# Control_Board_v0_2.net
KiCad netlist of a schematic drawn in EAGLE
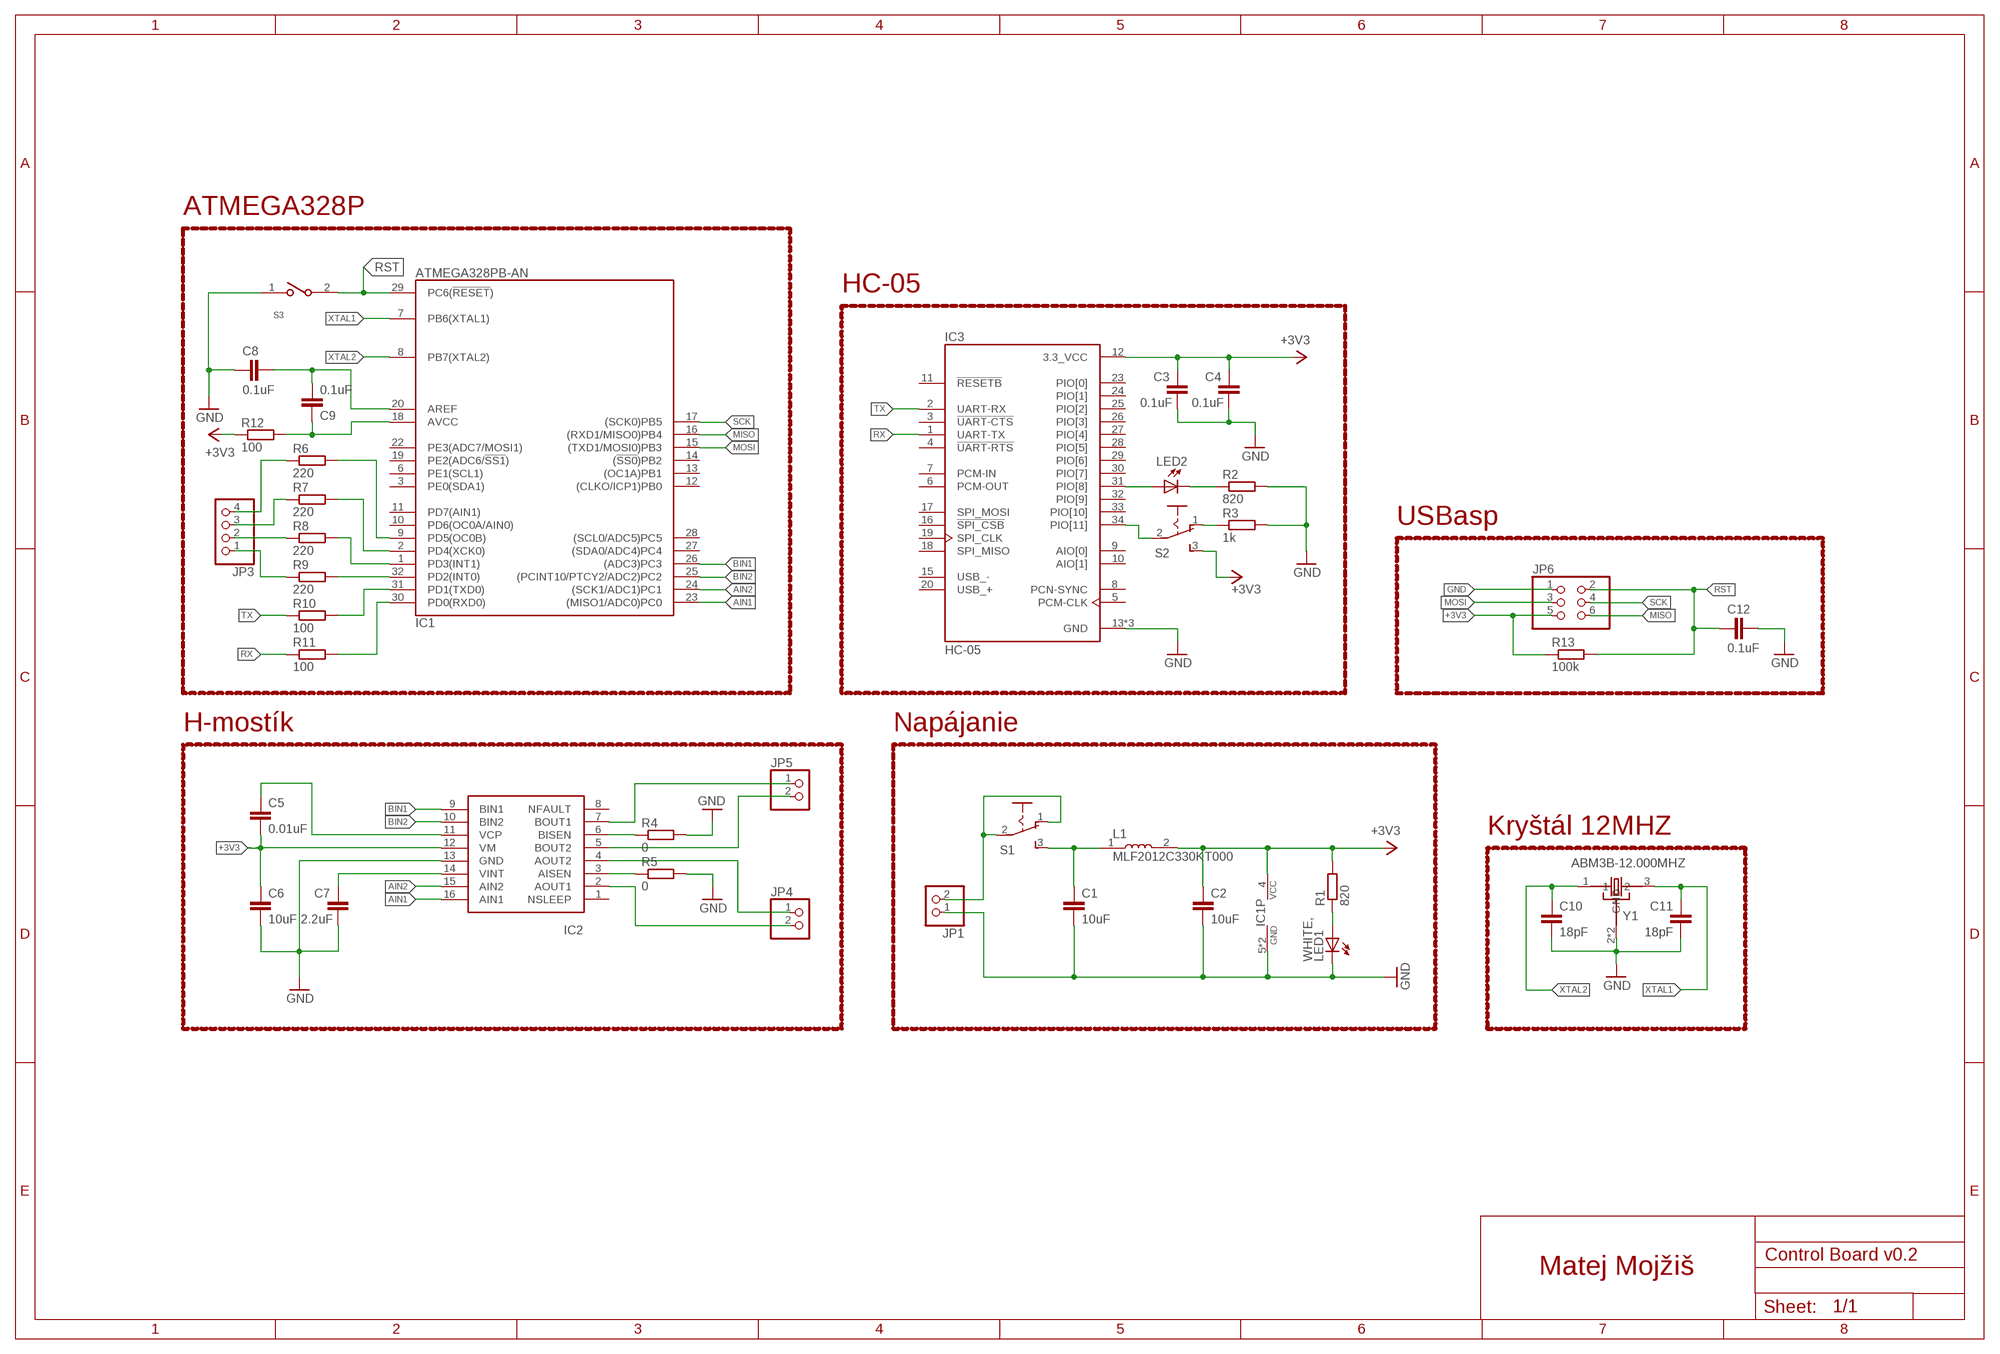
[diagram p0: schematic, sheet 1]

(export (version "E")
  (design (tool "Eeschema 10.0.6"))
  (components
    (comp (ref "C1")
      (value "10uF")
      (footprint "eagle-import:C0805")
      (libsource (lib "eagle-import") (part "C-EUC0805"))
    )
    (comp (ref "C2")
      (value "10uF")
      (footprint "eagle-import:C0805")
      (libsource (lib "eagle-import") (part "C-EUC0805"))
    )
    (comp (ref "C3")
      (value "0.1uF")
      (footprint "eagle-import:C0805")
      (libsource (lib "eagle-import") (part "C-EUC0805"))
    )
    (comp (ref "C4")
      (value "0.1uF")
      (footprint "eagle-import:C0805")
      (libsource (lib "eagle-import") (part "C-EUC0805"))
    )
    (comp (ref "C5")
      (value "0.01uF")
      (footprint "eagle-import:C0805")
      (libsource (lib "eagle-import") (part "C-EUC0805"))
    )
    (comp (ref "C6")
      (value "10uF")
      (footprint "eagle-import:C0805")
      (libsource (lib "eagle-import") (part "C-EUC0805"))
    )
    (comp (ref "C7")
      (value "2.2uF")
      (footprint "eagle-import:C0805")
      (libsource (lib "eagle-import") (part "C-EUC0805"))
    )
    (comp (ref "C8")
      (value "0.1uF")
      (footprint "eagle-import:C0805")
      (libsource (lib "eagle-import") (part "C-EUC0805"))
    )
    (comp (ref "C9")
      (value "0.1uF")
      (footprint "eagle-import:C0805")
      (libsource (lib "eagle-import") (part "C-EUC0805"))
    )
    (comp (ref "C10")
      (value "18pF")
      (footprint "eagle-import:C0805")
      (libsource (lib "eagle-import") (part "C-EUC0805"))
    )
    (comp (ref "C11")
      (value "18pF")
      (footprint "eagle-import:C0805")
      (libsource (lib "eagle-import") (part "C-EUC0805"))
    )
    (comp (ref "C12")
      (value "0.1uF")
      (footprint "eagle-import:C0805")
      (libsource (lib "eagle-import") (part "C-EUC0805"))
    )
    (comp (ref "IC1")
      (value "ATMEGA328PB-AN")
      (footprint "eagle-import:QFP32_7X7_0.80")
      (libsource (lib "eagle-import") (part "ATMEGA328PB-AN"))
    )
    (comp (ref "IC2")
      (value "DVR8833SUPERFICIAL")
      (footprint "eagle-import:PWP16")
      (libsource (lib "eagle-import") (part "DVR8833SUPERFICIAL"))
    )
    (comp (ref "IC3")
      (value "HC-05")
      (footprint "eagle-import:XCVR_HC-05")
      (fields (field (name "MF") "Bel Power solution"))
      (libsource (lib "eagle-import") (part "HC-05"))
    )
    (comp (ref "JP1")
      (value "PINHD-1X2/90")
      (footprint "eagle-import:1X02_90")
      (libsource (lib "eagle-import") (part "PINHD-1X2/90"))
    )
    (comp (ref "JP3")
      (value "PINHD-1X4")
      (footprint "eagle-import:1X04")
      (libsource (lib "eagle-import") (part "PINHD-1X4"))
    )
    (comp (ref "JP4")
      (value "PINHD-1X2/90")
      (footprint "eagle-import:1X02_90")
      (libsource (lib "eagle-import") (part "PINHD-1X2/90"))
    )
    (comp (ref "JP5")
      (value "PINHD-1X2/90")
      (footprint "eagle-import:1X02_90")
      (libsource (lib "eagle-import") (part "PINHD-1X2/90"))
    )
    (comp (ref "JP6")
      (value "PINHD-2X3")
      (footprint "eagle-import:2X03")
      (libsource (lib "eagle-import") (part "PINHD-2X3"))
    )
    (comp (ref "L1")
      (value "MLF2012C330KT000")
      (footprint "eagle-import:INDC2012X87N")
      (fields (field (name "MF") "TDK"))
      (libsource (lib "eagle-import") (part "MLF2012C330KT000"))
    )
    (comp (ref "LED1")
      (value "WHITE,")
      (footprint "eagle-import:CHIPLED_0805")
      (libsource (lib "eagle-import") (part "LEDCHIPLED_0805"))
    )
    (comp (ref "LED2")
      (value "RED")
      (footprint "eagle-import:CHIPLED_0805")
      (libsource (lib "eagle-import") (part "LEDCHIPLED_0805"))
    )
    (comp (ref "R1")
      (value "820")
      (footprint "eagle-import:R0805")
      (libsource (lib "eagle-import") (part "R-EU_R0805"))
    )
    (comp (ref "R2")
      (value "820")
      (footprint "eagle-import:R0805")
      (libsource (lib "eagle-import") (part "R-EU_R0805"))
    )
    (comp (ref "R3")
      (value "1k")
      (footprint "eagle-import:R0805")
      (libsource (lib "eagle-import") (part "R-EU_R0805"))
    )
    (comp (ref "R4")
      (value "0")
      (footprint "eagle-import:R0805")
      (libsource (lib "eagle-import") (part "R-EU_R0805"))
    )
    (comp (ref "R5")
      (value "0")
      (footprint "eagle-import:R0805")
      (libsource (lib "eagle-import") (part "R-EU_R0805"))
    )
    (comp (ref "R6")
      (value "220")
      (footprint "eagle-import:R0805")
      (libsource (lib "eagle-import") (part "R-EU_R0805"))
    )
    (comp (ref "R7")
      (value "220")
      (footprint "eagle-import:R0805")
      (libsource (lib "eagle-import") (part "R-EU_R0805"))
    )
    (comp (ref "R8")
      (value "220")
      (footprint "eagle-import:R0805")
      (libsource (lib "eagle-import") (part "R-EU_R0805"))
    )
    (comp (ref "R9")
      (value "220")
      (footprint "eagle-import:R0805")
      (libsource (lib "eagle-import") (part "R-EU_R0805"))
    )
    (comp (ref "R10")
      (value "100")
      (footprint "eagle-import:R0805")
      (libsource (lib "eagle-import") (part "R-EU_R0805"))
    )
    (comp (ref "R11")
      (value "100")
      (footprint "eagle-import:R0805")
      (libsource (lib "eagle-import") (part "R-EU_R0805"))
    )
    (comp (ref "R12")
      (value "100")
      (footprint "eagle-import:R0805")
      (libsource (lib "eagle-import") (part "R-EU_R0805"))
    )
    (comp (ref "R13")
      (value "100k")
      (footprint "eagle-import:R0805")
      (libsource (lib "eagle-import") (part "R-EU_R0805"))
    )
    (comp (ref "S1")
      (value "255SB")
      (footprint "eagle-import:255SB")
      (libsource (lib "eagle-import") (part "255SB"))
    )
    (comp (ref "S2")
      (value "255SB")
      (footprint "eagle-import:255SB")
      (libsource (lib "eagle-import") (part "255SB"))
    )
    (comp (ref "S3")
      (value "147873-2")
      (footprint "eagle-import:SW_147873-2")
      (fields (field (name "MF") "TE Connectivity"))
      (libsource (lib "eagle-import") (part "147873-2"))
    )
    (comp (ref "Y1")
      (value "ABM3B-12.000MHZ")
      (footprint "eagle-import:OSCSC500X320X110-4N")
      (fields (field (name "MF") "Abracon") (field (name "MP") "ABM3B-8.000MHZ-B2-T"))
      (libsource (lib "eagle-import") (part "ABM3B-8.000MHZ-B2-T"))
    )
  )
  (nets
    (net (code "1") (name "+3V3") (class "Default")
      (node (ref "C2") (pin "1") (pinfunction "1_1") (pintype "passive"))
      (node (ref "C3") (pin "1") (pinfunction "1_1") (pintype "passive"))
      (node (ref "C4") (pin "1") (pinfunction "1_1") (pintype "passive"))
      (node (ref "C5") (pin "2") (pinfunction "2_2") (pintype "passive"))
      (node (ref "C6") (pin "1") (pinfunction "1_1") (pintype "passive"))
      (node (ref "IC1") (pin "4") (pinfunction "VCC_4") (pintype "power_in"))
      (node (ref "IC2") (pin "12") (pinfunction "VM_12") (pintype "bidirectional"))
      (node (ref "IC3") (pin "12") (pinfunction "3.3_VCC_12") (pintype "power_in"))
      (node (ref "JP6") (pin "5") (pinfunction "5_5") (pintype "passive"))
      (node (ref "L1") (pin "2") (pinfunction "2_2") (pintype "passive"))
      (node (ref "R1") (pin "2") (pinfunction "2_2") (pintype "passive"))
      (node (ref "R12") (pin "1") (pinfunction "1_1") (pintype "passive"))
      (node (ref "R13") (pin "1") (pinfunction "1_1") (pintype "passive"))
      (node (ref "S2") (pin "3") (pinfunction "S_3") (pintype "passive"))
    )
    (net (code "2") (name "AIN1") (class "Default")
      (node (ref "IC1") (pin "23") (pinfunction "(MISO1/ADC0)PC0_23") (pintype "bidirectional"))
      (node (ref "IC2") (pin "16") (pinfunction "AIN1_16") (pintype "bidirectional"))
    )
    (net (code "3") (name "AIN2") (class "Default")
      (node (ref "IC1") (pin "24") (pinfunction "(SCK1/ADC1)PC1_24") (pintype "bidirectional"))
      (node (ref "IC2") (pin "15") (pinfunction "AIN2_15") (pintype "bidirectional"))
    )
    (net (code "4") (name "BIN1") (class "Default")
      (node (ref "IC1") (pin "26") (pinfunction "(ADC3)PC3_26") (pintype "bidirectional"))
      (node (ref "IC2") (pin "9") (pinfunction "BIN1_9") (pintype "bidirectional"))
    )
    (net (code "5") (name "BIN2") (class "Default")
      (node (ref "IC1") (pin "25") (pinfunction "(PCINT10/PTCY2/ADC2)PC2_25") (pintype "bidirectional"))
      (node (ref "IC2") (pin "10") (pinfunction "BIN2_10") (pintype "bidirectional"))
    )
    (net (code "6") (name "GND") (class "Default")
      (node (ref "C1") (pin "2") (pinfunction "2_2") (pintype "passive"))
      (node (ref "C10") (pin "2") (pinfunction "2_2") (pintype "passive"))
      (node (ref "C11") (pin "2") (pinfunction "2_2") (pintype "passive"))
      (node (ref "C12") (pin "1") (pinfunction "1_1") (pintype "passive"))
      (node (ref "C2") (pin "2") (pinfunction "2_2") (pintype "passive"))
      (node (ref "C3") (pin "2") (pinfunction "2_2") (pintype "passive"))
      (node (ref "C4") (pin "2") (pinfunction "2_2") (pintype "passive"))
      (node (ref "C6") (pin "2") (pinfunction "2_2") (pintype "passive"))
      (node (ref "C7") (pin "2") (pinfunction "2_2") (pintype "passive"))
      (node (ref "C8") (pin "2") (pinfunction "2_2") (pintype "passive"))
      (node (ref "IC1") (pin "21") (pinfunction "GND_21") (pintype "power_in"))
      (node (ref "IC1") (pin "5") (pinfunction "GND_5") (pintype "power_in"))
      (node (ref "IC2") (pin "13") (pinfunction "GND_13") (pintype "bidirectional"))
      (node (ref "IC3") (pin "13") (pinfunction "GND_13") (pintype "power_in"))
      (node (ref "IC3") (pin "21") (pinfunction "GND_21") (pintype "power_in"))
      (node (ref "IC3") (pin "22") (pinfunction "GND_22") (pintype "power_in"))
      (node (ref "JP1") (pin "1") (pinfunction "1_1") (pintype "passive"))
      (node (ref "JP6") (pin "1") (pinfunction "1_1") (pintype "passive"))
      (node (ref "LED1") (pin "C") (pinfunction "C_C") (pintype "passive"))
      (node (ref "R2") (pin "2") (pinfunction "2_2") (pintype "passive"))
      (node (ref "R3") (pin "2") (pinfunction "2_2") (pintype "passive"))
      (node (ref "R4") (pin "2") (pinfunction "2_2") (pintype "passive"))
      (node (ref "R5") (pin "2") (pinfunction "2_2") (pintype "passive"))
      (node (ref "S3") (pin "1") (pinfunction "1_1") (pintype "passive"))
      (node (ref "Y1") (pin "2") (pinfunction "GND_2") (pintype "passive"))
      (node (ref "Y1") (pin "4") (pinfunction "GND_4") (pintype "passive"))
    )
    (net (code "7") (name "MISO") (class "Default")
      (node (ref "IC1") (pin "16") (pinfunction "(RXD1/MISO0)PB4_16") (pintype "bidirectional"))
      (node (ref "JP6") (pin "6") (pinfunction "6_6") (pintype "passive"))
    )
    (net (code "8") (name "MOSI") (class "Default")
      (node (ref "IC1") (pin "15") (pinfunction "(TXD1/MOSI0)PB3_15") (pintype "bidirectional"))
      (node (ref "JP6") (pin "3") (pinfunction "3_3") (pintype "passive"))
    )
    (net (code "9") (name "Net-(IC1A-AREF)") (class "Default")
      (node (ref "C8") (pin "1") (pinfunction "1_1") (pintype "passive"))
      (node (ref "C9") (pin "2") (pinfunction "2_2") (pintype "passive"))
      (node (ref "IC1") (pin "20") (pinfunction "AREF_20") (pintype "passive"))
    )
    (net (code "10") (name "Net-(IC1A-AVCC)") (class "Default")
      (node (ref "C9") (pin "1") (pinfunction "1_1") (pintype "passive"))
      (node (ref "IC1") (pin "18") (pinfunction "AVCC_18") (pintype "power_in"))
      (node (ref "R12") (pin "2") (pinfunction "2_2") (pintype "passive"))
    )
    (net (code "11") (name "Net-(IC1A-PD0(RXD0))") (class "Default")
      (node (ref "IC1") (pin "30") (pinfunction "PD0(RXD0)_30") (pintype "bidirectional"))
      (node (ref "R11") (pin "2") (pinfunction "2_2") (pintype "passive"))
    )
    (net (code "12") (name "Net-(IC1A-PD1(TXD0))") (class "Default")
      (node (ref "IC1") (pin "31") (pinfunction "PD1(TXD0)_31") (pintype "bidirectional"))
      (node (ref "R10") (pin "2") (pinfunction "2_2") (pintype "passive"))
    )
    (net (code "13") (name "Net-(IC1A-PD2(INT0))") (class "Default")
      (node (ref "IC1") (pin "32") (pinfunction "PD2(INT0)_32") (pintype "bidirectional"))
      (node (ref "R9") (pin "2") (pinfunction "2_2") (pintype "passive"))
    )
    (net (code "14") (name "Net-(IC1A-PD3(INT1))") (class "Default")
      (node (ref "IC1") (pin "1") (pinfunction "PD3(INT1)_1") (pintype "bidirectional"))
      (node (ref "R8") (pin "2") (pinfunction "2_2") (pintype "passive"))
    )
    (net (code "15") (name "Net-(IC1A-PD4(XCK0))") (class "Default")
      (node (ref "IC1") (pin "2") (pinfunction "PD4(XCK0)_2") (pintype "bidirectional"))
      (node (ref "R7") (pin "2") (pinfunction "2_2") (pintype "passive"))
    )
    (net (code "16") (name "Net-(IC1A-PD5(OC0B))") (class "Default")
      (node (ref "IC1") (pin "9") (pinfunction "PD5(OC0B)_9") (pintype "bidirectional"))
      (node (ref "R6") (pin "2") (pinfunction "2_2") (pintype "passive"))
    )
    (net (code "17") (name "Net-(IC2-AISEN)") (class "Default")
      (node (ref "IC2") (pin "3") (pinfunction "AISEN_3") (pintype "bidirectional"))
      (node (ref "R5") (pin "1") (pinfunction "1_1") (pintype "passive"))
    )
    (net (code "18") (name "Net-(IC2-AOUT1)") (class "Default")
      (node (ref "IC2") (pin "2") (pinfunction "AOUT1_2") (pintype "bidirectional"))
      (node (ref "JP4") (pin "2") (pinfunction "2_2") (pintype "passive"))
    )
    (net (code "19") (name "Net-(IC2-AOUT2)") (class "Default")
      (node (ref "IC2") (pin "4") (pinfunction "AOUT2_4") (pintype "bidirectional"))
      (node (ref "JP4") (pin "1") (pinfunction "1_1") (pintype "passive"))
    )
    (net (code "20") (name "Net-(IC2-BISEN)") (class "Default")
      (node (ref "IC2") (pin "6") (pinfunction "BISEN_6") (pintype "bidirectional"))
      (node (ref "R4") (pin "1") (pinfunction "1_1") (pintype "passive"))
    )
    (net (code "21") (name "Net-(IC2-BOUT1)") (class "Default")
      (node (ref "IC2") (pin "7") (pinfunction "BOUT1_7") (pintype "bidirectional"))
      (node (ref "JP5") (pin "1") (pinfunction "1_1") (pintype "passive"))
    )
    (net (code "22") (name "Net-(IC2-BOUT2)") (class "Default")
      (node (ref "IC2") (pin "5") (pinfunction "BOUT2_5") (pintype "bidirectional"))
      (node (ref "JP5") (pin "2") (pinfunction "2_2") (pintype "passive"))
    )
    (net (code "23") (name "Net-(IC2-VCP)") (class "Default")
      (node (ref "C5") (pin "1") (pinfunction "1_1") (pintype "passive"))
      (node (ref "IC2") (pin "11") (pinfunction "VCP_11") (pintype "bidirectional"))
    )
    (net (code "24") (name "Net-(IC2-VINT)") (class "Default")
      (node (ref "C7") (pin "1") (pinfunction "1_1") (pintype "passive"))
      (node (ref "IC2") (pin "14") (pinfunction "VINT_14") (pintype "bidirectional"))
    )
    (net (code "25") (name "Net-(IC3-PIO[8])") (class "Default")
      (node (ref "IC3") (pin "31") (pinfunction "PIO[8]_31") (pintype "bidirectional"))
      (node (ref "LED2") (pin "A") (pinfunction "A_A") (pintype "passive"))
    )
    (net (code "26") (name "Net-(IC3-PIO[11])") (class "Default")
      (node (ref "IC3") (pin "34") (pinfunction "PIO[11]_34") (pintype "bidirectional"))
      (node (ref "S2") (pin "2") (pinfunction "P_2") (pintype "passive"))
    )
    (net (code "27") (name "Net-(JP3-Pad1)") (class "Default")
      (node (ref "JP3") (pin "1") (pinfunction "1_1") (pintype "passive"))
      (node (ref "R9") (pin "1") (pinfunction "1_1") (pintype "passive"))
    )
    (net (code "28") (name "Net-(JP3-Pad2)") (class "Default")
      (node (ref "JP3") (pin "2") (pinfunction "2_2") (pintype "passive"))
      (node (ref "R8") (pin "1") (pinfunction "1_1") (pintype "passive"))
    )
    (net (code "29") (name "Net-(JP3-Pad3)") (class "Default")
      (node (ref "JP3") (pin "3") (pinfunction "3_3") (pintype "passive"))
      (node (ref "R7") (pin "1") (pinfunction "1_1") (pintype "passive"))
    )
    (net (code "30") (name "Net-(JP3-Pad4)") (class "Default")
      (node (ref "JP3") (pin "4") (pinfunction "4_4") (pintype "passive"))
      (node (ref "R6") (pin "1") (pinfunction "1_1") (pintype "passive"))
    )
    (net (code "31") (name "Net-(LED1-PadA)") (class "Default")
      (node (ref "LED1") (pin "A") (pinfunction "A_A") (pintype "passive"))
      (node (ref "R1") (pin "1") (pinfunction "1_1") (pintype "passive"))
    )
    (net (code "32") (name "Net-(LED2-PadC)") (class "Default")
      (node (ref "LED2") (pin "C") (pinfunction "C_C") (pintype "passive"))
      (node (ref "R2") (pin "1") (pinfunction "1_1") (pintype "passive"))
    )
    (net (code "33") (name "Net-(S1-O)") (class "Default")
      (node (ref "JP1") (pin "2") (pinfunction "2_2") (pintype "passive"))
      (node (ref "S1") (pin "1") (pinfunction "O_1") (pintype "passive"))
      (node (ref "S1") (pin "2") (pinfunction "P_2") (pintype "passive"))
    )
    (net (code "34") (name "Net-(S1-S)") (class "Default")
      (node (ref "C1") (pin "1") (pinfunction "1_1") (pintype "passive"))
      (node (ref "L1") (pin "1") (pinfunction "1_1") (pintype "passive"))
      (node (ref "S1") (pin "3") (pinfunction "S_3") (pintype "passive"))
    )
    (net (code "35") (name "Net-(S2-O)") (class "Default")
      (node (ref "R3") (pin "1") (pinfunction "1_1") (pintype "passive"))
      (node (ref "S2") (pin "1") (pinfunction "O_1") (pintype "passive"))
    )
    (net (code "36") (name "RST") (class "Default")
      (node (ref "C12") (pin "2") (pinfunction "2_2") (pintype "passive"))
      (node (ref "IC1") (pin "29") (pinfunction "PC6(~{RESET})_29") (pintype "bidirectional"))
      (node (ref "JP6") (pin "2") (pinfunction "2_2") (pintype "passive"))
      (node (ref "R13") (pin "2") (pinfunction "2_2") (pintype "passive"))
      (node (ref "S3") (pin "2") (pinfunction "2_2") (pintype "passive"))
    )
    (net (code "37") (name "RX") (class "Default")
      (node (ref "IC3") (pin "1") (pinfunction "UART-TX_1") (pintype "output"))
      (node (ref "R11") (pin "1") (pinfunction "1_1") (pintype "passive"))
    )
    (net (code "38") (name "SCK") (class "Default")
      (node (ref "IC1") (pin "17") (pinfunction "(SCK0)PB5_17") (pintype "bidirectional"))
      (node (ref "JP6") (pin "4") (pinfunction "4_4") (pintype "passive"))
    )
    (net (code "39") (name "TX") (class "Default")
      (node (ref "IC3") (pin "2") (pinfunction "UART-RX_2") (pintype "input"))
      (node (ref "R10") (pin "1") (pinfunction "1_1") (pintype "passive"))
    )
    (net (code "40") (name "XTAL1") (class "Default")
      (node (ref "C11") (pin "1") (pinfunction "1_1") (pintype "passive"))
      (node (ref "IC1") (pin "7") (pinfunction "PB6(XTAL1)_7") (pintype "bidirectional"))
      (node (ref "Y1") (pin "3") (pinfunction "2_3") (pintype "passive"))
    )
    (net (code "41") (name "XTAL2") (class "Default")
      (node (ref "C10") (pin "1") (pinfunction "1_1") (pintype "passive"))
      (node (ref "IC1") (pin "8") (pinfunction "PB7(XTAL2)_8") (pintype "bidirectional"))
      (node (ref "Y1") (pin "1") (pinfunction "1_1") (pintype "passive"))
    )
    (net (code "42") (name "unconnected-(IC1A-(CLKO{slash}ICP1)PB0-Pad12)") (class "Default")
      (node (ref "IC1") (pin "12") (pinfunction "(CLKO/ICP1)PB0_12") (pintype "bidirectional"))
    )
    (net (code "43") (name "unconnected-(IC1A-(OC1A)PB1-Pad13)") (class "Default")
      (node (ref "IC1") (pin "13") (pinfunction "(OC1A)PB1_13") (pintype "bidirectional"))
    )
    (net (code "44") (name "unconnected-(IC1A-(SCL0{slash}ADC5)PC5-Pad28)") (class "Default")
      (node (ref "IC1") (pin "28") (pinfunction "(SCL0/ADC5)PC5_28") (pintype "bidirectional"))
    )
    (net (code "45") (name "unconnected-(IC1A-(SDA0{slash}ADC4)PC4-Pad27)") (class "Default")
      (node (ref "IC1") (pin "27") (pinfunction "(SDA0/ADC4)PC4_27") (pintype "bidirectional"))
    )
    (net (code "46") (name "unconnected-(IC1A-(~{SS0})PB2-Pad14)") (class "Default")
      (node (ref "IC1") (pin "14") (pinfunction "(~{SS0})PB2_14") (pintype "bidirectional"))
    )
    (net (code "47") (name "unconnected-(IC1A-PD6(OC0A{slash}AIN0)-Pad10)") (class "Default")
      (node (ref "IC1") (pin "10") (pinfunction "PD6(OC0A/AIN0)_10") (pintype "bidirectional"))
    )
    (net (code "48") (name "unconnected-(IC1A-PD7(AIN1)-Pad11)") (class "Default")
      (node (ref "IC1") (pin "11") (pinfunction "PD7(AIN1)_11") (pintype "bidirectional"))
    )
    (net (code "49") (name "unconnected-(IC1A-PE0(SDA1)-Pad3)") (class "Default")
      (node (ref "IC1") (pin "3") (pinfunction "PE0(SDA1)_3") (pintype "bidirectional"))
    )
    (net (code "50") (name "unconnected-(IC1A-PE1(SCL1)-Pad6)") (class "Default")
      (node (ref "IC1") (pin "6") (pinfunction "PE1(SCL1)_6") (pintype "bidirectional"))
    )
    (net (code "51") (name "unconnected-(IC1A-PE2(ADC6{slash}~{SS1})-Pad19)") (class "Default")
      (node (ref "IC1") (pin "19") (pinfunction "PE2(ADC6/~{SS1})_19") (pintype "bidirectional"))
    )
    (net (code "52") (name "unconnected-(IC1A-PE3(ADC7{slash}MOSI1)-Pad22)") (class "Default")
      (node (ref "IC1") (pin "22") (pinfunction "PE3(ADC7/MOSI1)_22") (pintype "bidirectional"))
    )
    (net (code "53") (name "unconnected-(IC2-NFAULT-Pad8)") (class "Default")
      (node (ref "IC2") (pin "8") (pinfunction "NFAULT_8") (pintype "bidirectional"))
    )
    (net (code "54") (name "unconnected-(IC2-NSLEEP-Pad1)") (class "Default")
      (node (ref "IC2") (pin "1") (pinfunction "NSLEEP_1") (pintype "bidirectional"))
    )
    (net (code "55") (name "unconnected-(IC3-AIO[0]-Pad9)") (class "Default")
      (node (ref "IC3") (pin "9") (pinfunction "AIO[0]_9") (pintype "bidirectional"))
    )
    (net (code "56") (name "unconnected-(IC3-AIO[1]-Pad10)") (class "Default")
      (node (ref "IC3") (pin "10") (pinfunction "AIO[1]_10") (pintype "bidirectional"))
    )
    (net (code "57") (name "unconnected-(IC3-PCM-CLK-Pad5)") (class "Default")
      (node (ref "IC3") (pin "5") (pinfunction "PCM-CLK_5") (pintype "bidirectional"))
    )
    (net (code "58") (name "unconnected-(IC3-PCM-IN-Pad7)") (class "Default")
      (node (ref "IC3") (pin "7") (pinfunction "PCM-IN_7") (pintype "input"))
    )
    (net (code "59") (name "unconnected-(IC3-PCM-OUT-Pad6)") (class "Default")
      (node (ref "IC3") (pin "6") (pinfunction "PCM-OUT_6") (pintype "output"))
    )
    (net (code "60") (name "unconnected-(IC3-PCN-SYNC-Pad8)") (class "Default")
      (node (ref "IC3") (pin "8") (pinfunction "PCN-SYNC_8") (pintype "bidirectional"))
    )
    (net (code "61") (name "unconnected-(IC3-PIO[0]-Pad23)") (class "Default")
      (node (ref "IC3") (pin "23") (pinfunction "PIO[0]_23") (pintype "bidirectional"))
    )
    (net (code "62") (name "unconnected-(IC3-PIO[1]-Pad24)") (class "Default")
      (node (ref "IC3") (pin "24") (pinfunction "PIO[1]_24") (pintype "bidirectional"))
    )
    (net (code "63") (name "unconnected-(IC3-PIO[2]-Pad25)") (class "Default")
      (node (ref "IC3") (pin "25") (pinfunction "PIO[2]_25") (pintype "bidirectional"))
    )
    (net (code "64") (name "unconnected-(IC3-PIO[3]-Pad26)") (class "Default")
      (node (ref "IC3") (pin "26") (pinfunction "PIO[3]_26") (pintype "bidirectional"))
    )
    (net (code "65") (name "unconnected-(IC3-PIO[4]-Pad27)") (class "Default")
      (node (ref "IC3") (pin "27") (pinfunction "PIO[4]_27") (pintype "bidirectional"))
    )
    (net (code "66") (name "unconnected-(IC3-PIO[5]-Pad28)") (class "Default")
      (node (ref "IC3") (pin "28") (pinfunction "PIO[5]_28") (pintype "bidirectional"))
    )
    (net (code "67") (name "unconnected-(IC3-PIO[6]-Pad29)") (class "Default")
      (node (ref "IC3") (pin "29") (pinfunction "PIO[6]_29") (pintype "bidirectional"))
    )
    (net (code "68") (name "unconnected-(IC3-PIO[7]-Pad30)") (class "Default")
      (node (ref "IC3") (pin "30") (pinfunction "PIO[7]_30") (pintype "bidirectional"))
    )
    (net (code "69") (name "unconnected-(IC3-PIO[9]-Pad32)") (class "Default")
      (node (ref "IC3") (pin "32") (pinfunction "PIO[9]_32") (pintype "bidirectional"))
    )
    (net (code "70") (name "unconnected-(IC3-PIO[10]-Pad33)") (class "Default")
      (node (ref "IC3") (pin "33") (pinfunction "PIO[10]_33") (pintype "bidirectional"))
    )
    (net (code "71") (name "unconnected-(IC3-SPI_CLK-Pad19)") (class "Default")
      (node (ref "IC3") (pin "19") (pinfunction "SPI_CLK_19") (pintype "input"))
    )
    (net (code "72") (name "unconnected-(IC3-SPI_MISO-Pad18)") (class "Default")
      (node (ref "IC3") (pin "18") (pinfunction "SPI_MISO_18") (pintype "output"))
    )
    (net (code "73") (name "unconnected-(IC3-SPI_MOSI-Pad17)") (class "Default")
      (node (ref "IC3") (pin "17") (pinfunction "SPI_MOSI_17") (pintype "input"))
    )
    (net (code "74") (name "unconnected-(IC3-USB_+-Pad20)") (class "Default")
      (node (ref "IC3") (pin "20") (pinfunction "USB_+_20") (pintype "bidirectional"))
    )
    (net (code "75") (name "unconnected-(IC3-USB_--Pad15)") (class "Default")
      (node (ref "IC3") (pin "15") (pinfunction "USB_-_15") (pintype "bidirectional"))
    )
    (net (code "76") (name "unconnected-(IC3-~{RESETB}-Pad11)") (class "Default")
      (node (ref "IC3") (pin "11") (pinfunction "~{RESETB}_11") (pintype "input"))
    )
    (net (code "77") (name "unconnected-(IC3-~{SPI_CSB}-Pad16)") (class "Default")
      (node (ref "IC3") (pin "16") (pinfunction "~{SPI_CSB}_16") (pintype "input"))
    )
    (net (code "78") (name "unconnected-(IC3-~{UART-CTS}-Pad3)") (class "Default")
      (node (ref "IC3") (pin "3") (pinfunction "~{UART-CTS}_3") (pintype "input"))
    )
    (net (code "79") (name "unconnected-(IC3-~{UART-RTS}-Pad4)") (class "Default")
      (node (ref "IC3") (pin "4") (pinfunction "~{UART-RTS}_4") (pintype "output"))
    )
  )
)
